# template_50x45.net
KiCad netlist of a schematic drawn in EAGLE
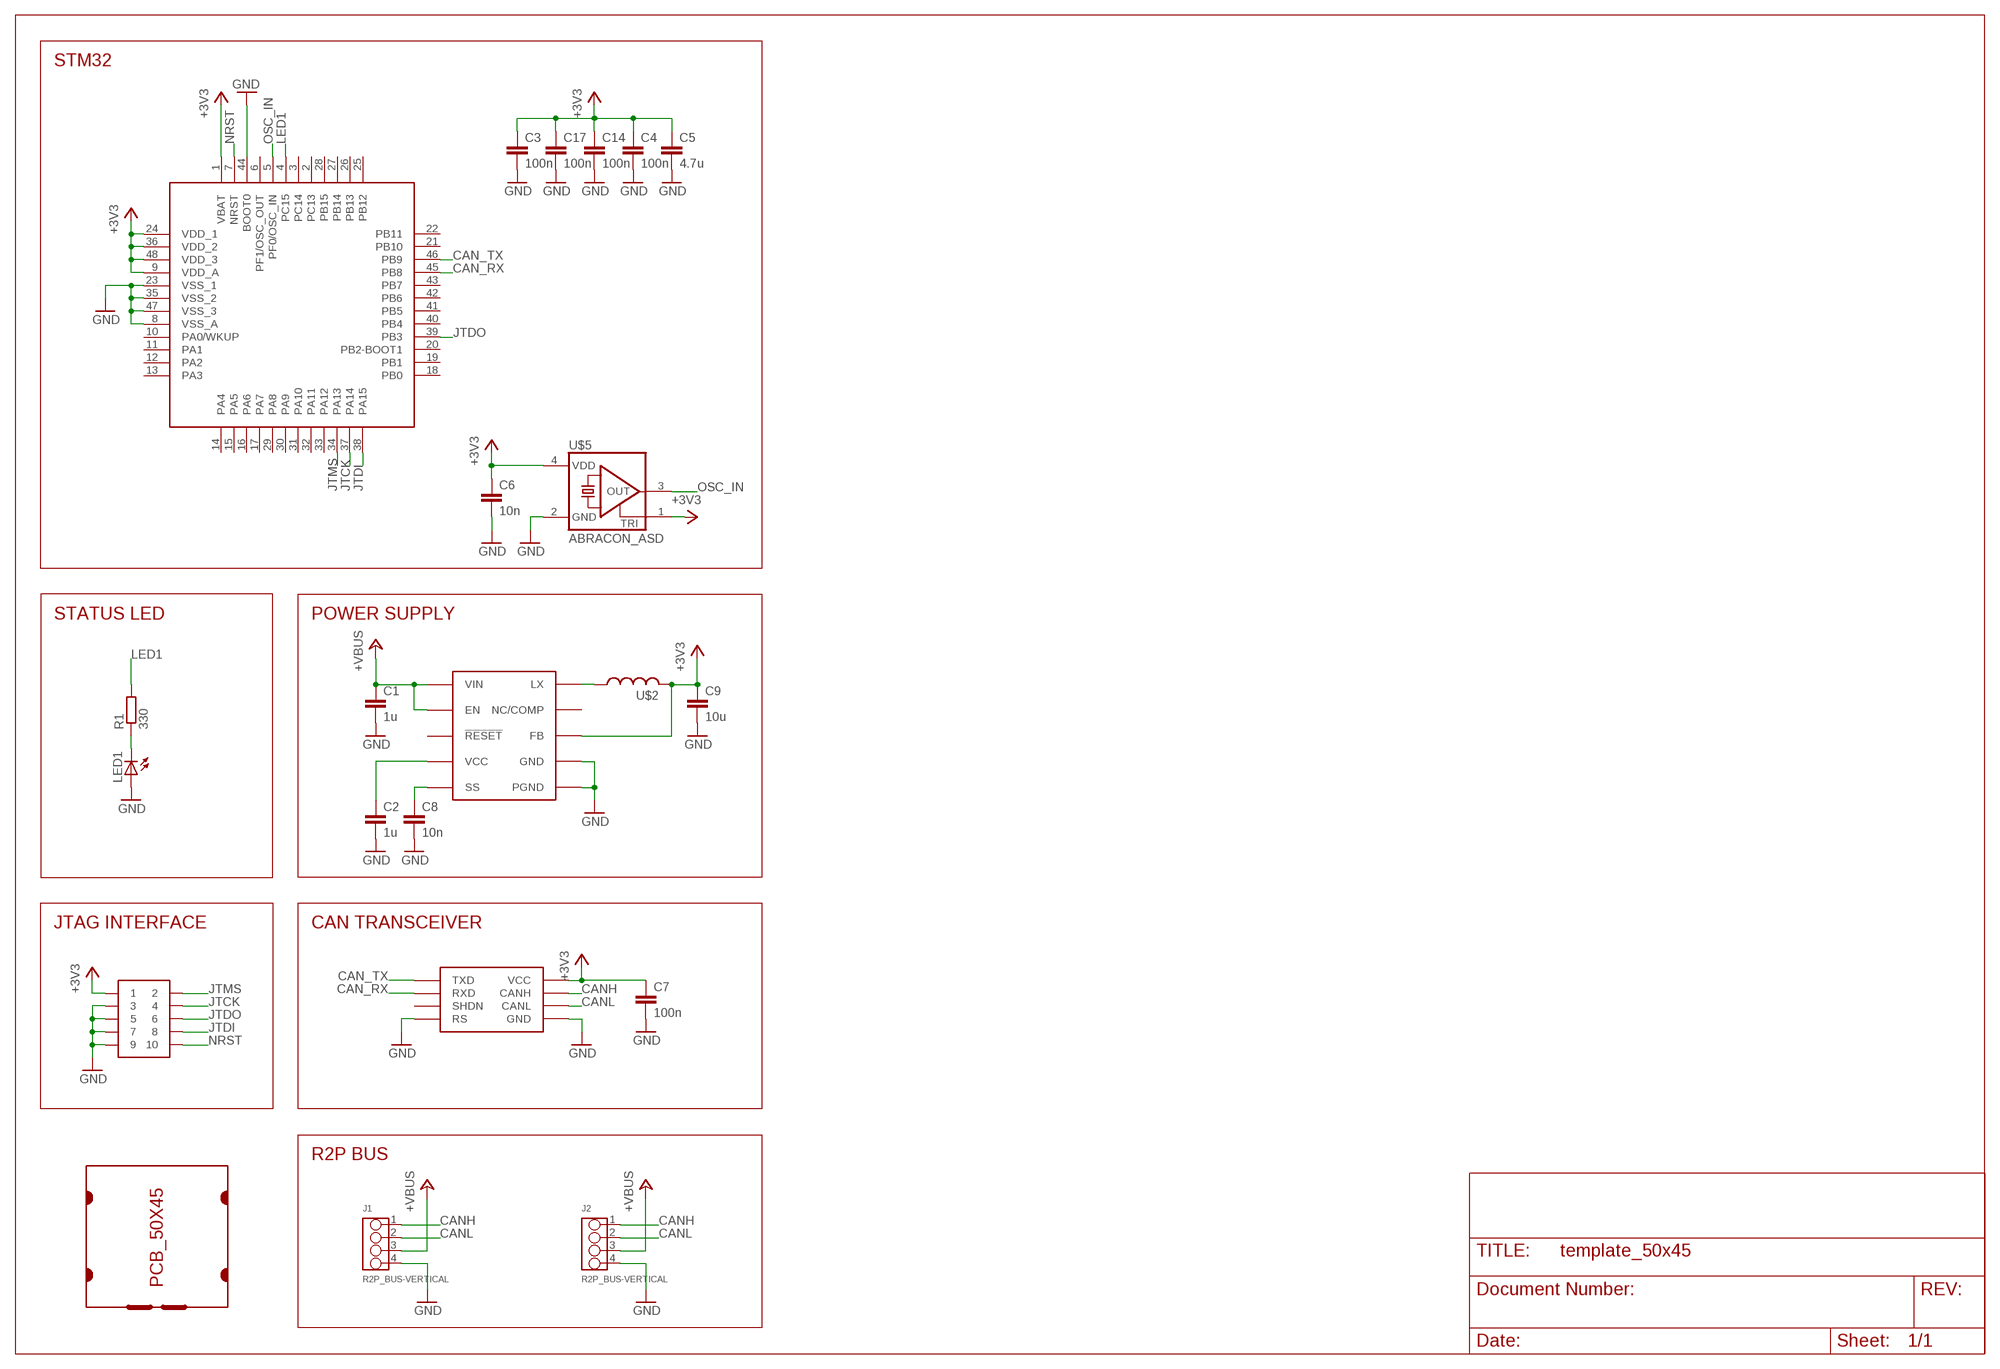
[diagram p0: schematic, sheet 1]

(export (version "E")
  (design (tool "Eeschema 10.0.6"))
  (components
    (comp (ref "C1")
      (value "1u")
      (footprint "eagle-import:C1206")
      (libsource (lib "eagle-import") (part "C1206"))
    )
    (comp (ref "C2")
      (value "1u")
      (footprint "eagle-import:C0603")
      (libsource (lib "eagle-import") (part "C0603"))
    )
    (comp (ref "C3")
      (value "100n")
      (footprint "eagle-import:C0603")
      (libsource (lib "eagle-import") (part "C0603"))
    )
    (comp (ref "C4")
      (value "100n")
      (footprint "eagle-import:C0603")
      (libsource (lib "eagle-import") (part "C0603"))
    )
    (comp (ref "C5")
      (value "4.7u")
      (footprint "eagle-import:C0805")
      (libsource (lib "eagle-import") (part "C0805"))
    )
    (comp (ref "C6")
      (value "10n")
      (footprint "eagle-import:C0603")
      (libsource (lib "eagle-import") (part "C0603"))
    )
    (comp (ref "C7")
      (value "100n")
      (footprint "eagle-import:C0603")
      (libsource (lib "eagle-import") (part "C0603"))
    )
    (comp (ref "C8")
      (value "10n")
      (footprint "eagle-import:C0603")
      (libsource (lib "eagle-import") (part "C0603"))
    )
    (comp (ref "C9")
      (value "10u")
      (footprint "eagle-import:C0805")
      (libsource (lib "eagle-import") (part "C0805"))
    )
    (comp (ref "C14")
      (value "100n")
      (footprint "eagle-import:C0603")
      (libsource (lib "eagle-import") (part "C0603"))
    )
    (comp (ref "C17")
      (value "100n")
      (footprint "eagle-import:C0603")
      (libsource (lib "eagle-import") (part "C0603"))
    )
    (comp (ref "J1")
      (value "R2P_BUS-VERTICAL")
      (footprint "eagle-import:OPL-EAGLE-LIBRARY_4P-2.0")
      (libsource (lib "eagle-import") (part "R2P_BUS-VERTICAL"))
    )
    (comp (ref "J2")
      (value "R2P_BUS-VERTICAL")
      (footprint "eagle-import:OPL-EAGLE-LIBRARY_4P-2.0")
      (libsource (lib "eagle-import") (part "R2P_BUS-VERTICAL"))
    )
    (comp (ref "LED1")
      (value "LED0805")
      (footprint "eagle-import:CHIPLED_0805")
      (libsource (lib "eagle-import") (part "LED0805"))
    )
    (comp (ref "R1")
      (value "330")
      (footprint "eagle-import:R0603")
      (libsource (lib "eagle-import") (part "R0603"))
    )
    (comp (ref "SOT1")
      (value "MAX3051EKA")
      (footprint "eagle-import:SOT23-8L")
      (libsource (lib "eagle-import") (part "MAX3051EKA"))
    )
    (comp (ref "U$1")
      (value "PCB_50X45")
      (footprint "eagle-import:50X45")
      (libsource (lib "eagle-import") (part "PCB_50X45"))
    )
    (comp (ref "U$2")
      (value "LPS4018")
      (footprint "eagle-import:COILCRAFT_LPS4018")
      (libsource (lib "eagle-import") (part "LPS4018"))
    )
    (comp (ref "U$3")
      (value "MAX17501")
      (footprint "eagle-import:TDFN-10")
      (libsource (lib "eagle-import") (part "MAX17501"))
    )
    (comp (ref "U$4")
      (value "JTAG-TH")
      (footprint "eagle-import:SAMTEC_FTSH-105-TH")
      (libsource (lib "eagle-import") (part "JTAG-TH"))
    )
    (comp (ref "U$5")
      (value "ABRACON_ASD")
      (footprint "eagle-import:ABRACON_2.5X2")
      (libsource (lib "eagle-import") (part "ABRACON_ASD"))
    )
    (comp (ref "U$6")
      (value "STM32F303CTX")
      (footprint "eagle-import:LQFP48")
      (libsource (lib "eagle-import") (part "STM32F303CTX"))
    )
  )
  (nets
    (net (code "1") (name "+3V3") (class "Default")
      (node (ref "C14") (pin "1") (pinfunction "1_1") (pintype "passive"))
      (node (ref "C17") (pin "1") (pinfunction "1_1") (pintype "passive"))
      (node (ref "C3") (pin "1") (pinfunction "1_1") (pintype "passive"))
      (node (ref "C4") (pin "1") (pinfunction "1_1") (pintype "passive"))
      (node (ref "C5") (pin "1") (pinfunction "1_1") (pintype "passive"))
      (node (ref "C6") (pin "1") (pinfunction "1_1") (pintype "passive"))
      (node (ref "C7") (pin "1") (pinfunction "1_1") (pintype "passive"))
      (node (ref "C9") (pin "1") (pinfunction "1_1") (pintype "passive"))
      (node (ref "SOT1") (pin "3") (pinfunction "VCC_3") (pintype "bidirectional"))
      (node (ref "U$2") (pin "P$2") (pinfunction "2_P$2") (pintype "passive"))
      (node (ref "U$3") (pin "P$5") (pinfunction "FB_P$5") (pintype "bidirectional"))
      (node (ref "U$4") (pin "1") (pinfunction "1_1") (pintype "bidirectional"))
      (node (ref "U$5") (pin "1") (pinfunction "TRI_1") (pintype "input"))
      (node (ref "U$5") (pin "4") (pinfunction "VDD_4") (pintype "power_in"))
      (node (ref "U$6") (pin "1") (pinfunction "VBAT_1") (pintype "bidirectional"))
      (node (ref "U$6") (pin "24") (pinfunction "VDD_1_24") (pintype "bidirectional"))
      (node (ref "U$6") (pin "36") (pinfunction "VDD_2_36") (pintype "bidirectional"))
      (node (ref "U$6") (pin "48") (pinfunction "VDD_3_48") (pintype "bidirectional"))
      (node (ref "U$6") (pin "9") (pinfunction "VDD_A_9") (pintype "bidirectional"))
    )
    (net (code "2") (name "+VBUS") (class "Default")
      (node (ref "C1") (pin "1") (pinfunction "1_1") (pintype "passive"))
      (node (ref "J1") (pin "3") (pinfunction "3_3") (pintype "bidirectional"))
      (node (ref "J2") (pin "3") (pinfunction "3_3") (pintype "bidirectional"))
      (node (ref "U$3") (pin "P$2") (pinfunction "VIN_P$2") (pintype "bidirectional"))
      (node (ref "U$3") (pin "P$3") (pinfunction "EN_P$3") (pintype "bidirectional"))
    )
    (net (code "3") (name "/CANH") (class "Default")
      (node (ref "J1") (pin "1") (pinfunction "1_1") (pintype "bidirectional"))
      (node (ref "J2") (pin "1") (pinfunction "1_1") (pintype "bidirectional"))
      (node (ref "SOT1") (pin "7") (pinfunction "CANH_7") (pintype "bidirectional"))
    )
    (net (code "4") (name "/CANL") (class "Default")
      (node (ref "J1") (pin "2") (pinfunction "2_2") (pintype "bidirectional"))
      (node (ref "J2") (pin "2") (pinfunction "2_2") (pintype "bidirectional"))
      (node (ref "SOT1") (pin "6") (pinfunction "CANL_6") (pintype "bidirectional"))
    )
    (net (code "5") (name "/CAN_RX") (class "Default")
      (node (ref "SOT1") (pin "4") (pinfunction "RXD_4") (pintype "bidirectional"))
      (node (ref "U$6") (pin "45") (pinfunction "PB8_45") (pintype "bidirectional"))
    )
    (net (code "6") (name "/CAN_TX") (class "Default")
      (node (ref "SOT1") (pin "1") (pinfunction "TXD_1") (pintype "bidirectional"))
      (node (ref "U$6") (pin "46") (pinfunction "PB9_46") (pintype "bidirectional"))
    )
    (net (code "7") (name "/JTCK") (class "Default")
      (node (ref "U$4") (pin "4") (pinfunction "4_4") (pintype "bidirectional"))
      (node (ref "U$6") (pin "37") (pinfunction "PA14_37") (pintype "bidirectional"))
    )
    (net (code "8") (name "/JTDI") (class "Default")
      (node (ref "U$4") (pin "8") (pinfunction "8_8") (pintype "bidirectional"))
      (node (ref "U$6") (pin "38") (pinfunction "PA15_38") (pintype "bidirectional"))
    )
    (net (code "9") (name "/JTDO") (class "Default")
      (node (ref "U$4") (pin "6") (pinfunction "6_6") (pintype "bidirectional"))
      (node (ref "U$6") (pin "39") (pinfunction "PB3_39") (pintype "bidirectional"))
    )
    (net (code "10") (name "/JTMS") (class "Default")
      (node (ref "U$4") (pin "2") (pinfunction "2_2") (pintype "bidirectional"))
      (node (ref "U$6") (pin "34") (pinfunction "PA13_34") (pintype "bidirectional"))
    )
    (net (code "11") (name "/LED1") (class "Default")
      (node (ref "R1") (pin "2") (pinfunction "2_2") (pintype "passive"))
      (node (ref "U$6") (pin "4") (pinfunction "PC15_4") (pintype "bidirectional"))
    )
    (net (code "12") (name "/NRST") (class "Default")
      (node (ref "U$4") (pin "10") (pinfunction "10_10") (pintype "bidirectional"))
      (node (ref "U$6") (pin "7") (pinfunction "NRST_7") (pintype "bidirectional"))
    )
    (net (code "13") (name "/OSC_IN") (class "Default")
      (node (ref "U$5") (pin "3") (pinfunction "OUT_3") (pintype "output"))
      (node (ref "U$6") (pin "5") (pinfunction "PF0/OSC_IN_5") (pintype "bidirectional"))
    )
    (net (code "14") (name "GND") (class "Default")
      (node (ref "C1") (pin "2") (pinfunction "2_2") (pintype "passive"))
      (node (ref "C14") (pin "2") (pinfunction "2_2") (pintype "passive"))
      (node (ref "C17") (pin "2") (pinfunction "2_2") (pintype "passive"))
      (node (ref "C2") (pin "2") (pinfunction "2_2") (pintype "passive"))
      (node (ref "C3") (pin "2") (pinfunction "2_2") (pintype "passive"))
      (node (ref "C4") (pin "2") (pinfunction "2_2") (pintype "passive"))
      (node (ref "C5") (pin "2") (pinfunction "2_2") (pintype "passive"))
      (node (ref "C6") (pin "2") (pinfunction "2_2") (pintype "passive"))
      (node (ref "C7") (pin "2") (pinfunction "2_2") (pintype "passive"))
      (node (ref "C8") (pin "2") (pinfunction "2_2") (pintype "passive"))
      (node (ref "C9") (pin "2") (pinfunction "2_2") (pintype "passive"))
      (node (ref "J1") (pin "4") (pinfunction "4_4") (pintype "bidirectional"))
      (node (ref "J2") (pin "4") (pinfunction "4_4") (pintype "bidirectional"))
      (node (ref "LED1") (pin "A") (pinfunction "A_A") (pintype "passive"))
      (node (ref "SOT1") (pin "2") (pinfunction "GND_2") (pintype "bidirectional"))
      (node (ref "SOT1") (pin "8") (pinfunction "RS_8") (pintype "bidirectional"))
      (node (ref "U$3") (pin "P$1") (pinfunction "PGND_P$1") (pintype "bidirectional"))
      (node (ref "U$3") (pin "P$11") (pinfunction "PGND_P$11") (pintype "bidirectional"))
      (node (ref "U$3") (pin "P$9") (pinfunction "GND_P$9") (pintype "bidirectional"))
      (node (ref "U$4") (pin "3") (pinfunction "3_3") (pintype "bidirectional"))
      (node (ref "U$4") (pin "5") (pinfunction "5_5") (pintype "bidirectional"))
      (node (ref "U$4") (pin "7") (pinfunction "7_7") (pintype "bidirectional"))
      (node (ref "U$4") (pin "9") (pinfunction "9_9") (pintype "bidirectional"))
      (node (ref "U$5") (pin "2") (pinfunction "GND_2") (pintype "power_in"))
      (node (ref "U$6") (pin "23") (pinfunction "VSS_1_23") (pintype "bidirectional"))
      (node (ref "U$6") (pin "35") (pinfunction "VSS_2_35") (pintype "bidirectional"))
      (node (ref "U$6") (pin "44") (pinfunction "BOOT0_44") (pintype "bidirectional"))
      (node (ref "U$6") (pin "47") (pinfunction "VSS_3_47") (pintype "bidirectional"))
      (node (ref "U$6") (pin "8") (pinfunction "VSS_A_8") (pintype "bidirectional"))
    )
    (net (code "15") (name "Net-(LED1-PadC)") (class "Default")
      (node (ref "LED1") (pin "C") (pinfunction "C_C") (pintype "passive"))
      (node (ref "R1") (pin "1") (pinfunction "1_1") (pintype "passive"))
    )
    (net (code "16") (name "Net-(U$2-1)") (class "Default")
      (node (ref "U$2") (pin "P$1") (pinfunction "1_P$1") (pintype "passive"))
      (node (ref "U$3") (pin "P$10") (pinfunction "LX_P$10") (pintype "bidirectional"))
    )
    (net (code "17") (name "Net-(U$3-SS)") (class "Default")
      (node (ref "C8") (pin "1") (pinfunction "1_1") (pintype "passive"))
      (node (ref "U$3") (pin "P$6") (pinfunction "SS_P$6") (pintype "bidirectional"))
    )
    (net (code "18") (name "Net-(U$3-VCC)") (class "Default")
      (node (ref "C2") (pin "1") (pinfunction "1_1") (pintype "passive"))
      (node (ref "U$3") (pin "P$4") (pinfunction "VCC_P$4") (pintype "bidirectional"))
    )
    (net (code "19") (name "unconnected-(SOT1-SHDN-Pad5)") (class "Default")
      (node (ref "SOT1") (pin "5") (pinfunction "SHDN_5") (pintype "bidirectional"))
    )
    (net (code "20") (name "unconnected-(U$3-NC{slash}COMP-PadP$7)") (class "Default")
      (node (ref "U$3") (pin "P$7") (pinfunction "NC/COMP_P$7") (pintype "bidirectional"))
    )
    (net (code "21") (name "unconnected-(U$3-~{RESET}-PadP$8)") (class "Default")
      (node (ref "U$3") (pin "P$8") (pinfunction "~{RESET}_P$8") (pintype "bidirectional"))
    )
    (net (code "22") (name "unconnected-(U$6-PA0{slash}WKUP-Pad10)") (class "Default")
      (node (ref "U$6") (pin "10") (pinfunction "PA0/WKUP_10") (pintype "bidirectional"))
    )
    (net (code "23") (name "unconnected-(U$6-PA1-Pad11)") (class "Default")
      (node (ref "U$6") (pin "11") (pinfunction "PA1_11") (pintype "bidirectional"))
    )
    (net (code "24") (name "unconnected-(U$6-PA2-Pad12)") (class "Default")
      (node (ref "U$6") (pin "12") (pinfunction "PA2_12") (pintype "bidirectional"))
    )
    (net (code "25") (name "unconnected-(U$6-PA3-Pad13)") (class "Default")
      (node (ref "U$6") (pin "13") (pinfunction "PA3_13") (pintype "bidirectional"))
    )
    (net (code "26") (name "unconnected-(U$6-PA4-Pad14)") (class "Default")
      (node (ref "U$6") (pin "14") (pinfunction "PA4_14") (pintype "bidirectional"))
    )
    (net (code "27") (name "unconnected-(U$6-PA5-Pad15)") (class "Default")
      (node (ref "U$6") (pin "15") (pinfunction "PA5_15") (pintype "bidirectional"))
    )
    (net (code "28") (name "unconnected-(U$6-PA6-Pad16)") (class "Default")
      (node (ref "U$6") (pin "16") (pinfunction "PA6_16") (pintype "bidirectional"))
    )
    (net (code "29") (name "unconnected-(U$6-PA7-Pad17)") (class "Default")
      (node (ref "U$6") (pin "17") (pinfunction "PA7_17") (pintype "bidirectional"))
    )
    (net (code "30") (name "unconnected-(U$6-PA8-Pad29)") (class "Default")
      (node (ref "U$6") (pin "29") (pinfunction "PA8_29") (pintype "bidirectional"))
    )
    (net (code "31") (name "unconnected-(U$6-PA9-Pad30)") (class "Default")
      (node (ref "U$6") (pin "30") (pinfunction "PA9_30") (pintype "bidirectional"))
    )
    (net (code "32") (name "unconnected-(U$6-PA10-Pad31)") (class "Default")
      (node (ref "U$6") (pin "31") (pinfunction "PA10_31") (pintype "bidirectional"))
    )
    (net (code "33") (name "unconnected-(U$6-PA11-Pad32)") (class "Default")
      (node (ref "U$6") (pin "32") (pinfunction "PA11_32") (pintype "bidirectional"))
    )
    (net (code "34") (name "unconnected-(U$6-PA12-Pad33)") (class "Default")
      (node (ref "U$6") (pin "33") (pinfunction "PA12_33") (pintype "bidirectional"))
    )
    (net (code "35") (name "unconnected-(U$6-PB0-Pad18)") (class "Default")
      (node (ref "U$6") (pin "18") (pinfunction "PB0_18") (pintype "bidirectional"))
    )
    (net (code "36") (name "unconnected-(U$6-PB1-Pad19)") (class "Default")
      (node (ref "U$6") (pin "19") (pinfunction "PB1_19") (pintype "bidirectional"))
    )
    (net (code "37") (name "unconnected-(U$6-PB2-BOOT1-Pad20)") (class "Default")
      (node (ref "U$6") (pin "20") (pinfunction "PB2-BOOT1_20") (pintype "bidirectional"))
    )
    (net (code "38") (name "unconnected-(U$6-PB4-Pad40)") (class "Default")
      (node (ref "U$6") (pin "40") (pinfunction "PB4_40") (pintype "bidirectional"))
    )
    (net (code "39") (name "unconnected-(U$6-PB5-Pad41)") (class "Default")
      (node (ref "U$6") (pin "41") (pinfunction "PB5_41") (pintype "bidirectional"))
    )
    (net (code "40") (name "unconnected-(U$6-PB6-Pad42)") (class "Default")
      (node (ref "U$6") (pin "42") (pinfunction "PB6_42") (pintype "bidirectional"))
    )
    (net (code "41") (name "unconnected-(U$6-PB7-Pad43)") (class "Default")
      (node (ref "U$6") (pin "43") (pinfunction "PB7_43") (pintype "bidirectional"))
    )
    (net (code "42") (name "unconnected-(U$6-PB10-Pad21)") (class "Default")
      (node (ref "U$6") (pin "21") (pinfunction "PB10_21") (pintype "bidirectional"))
    )
    (net (code "43") (name "unconnected-(U$6-PB11-Pad22)") (class "Default")
      (node (ref "U$6") (pin "22") (pinfunction "PB11_22") (pintype "bidirectional"))
    )
    (net (code "44") (name "unconnected-(U$6-PB12-Pad25)") (class "Default")
      (node (ref "U$6") (pin "25") (pinfunction "PB12_25") (pintype "bidirectional"))
    )
    (net (code "45") (name "unconnected-(U$6-PB13-Pad26)") (class "Default")
      (node (ref "U$6") (pin "26") (pinfunction "PB13_26") (pintype "bidirectional"))
    )
    (net (code "46") (name "unconnected-(U$6-PB14-Pad27)") (class "Default")
      (node (ref "U$6") (pin "27") (pinfunction "PB14_27") (pintype "bidirectional"))
    )
    (net (code "47") (name "unconnected-(U$6-PB15-Pad28)") (class "Default")
      (node (ref "U$6") (pin "28") (pinfunction "PB15_28") (pintype "bidirectional"))
    )
    (net (code "48") (name "unconnected-(U$6-PC13-Pad2)") (class "Default")
      (node (ref "U$6") (pin "2") (pinfunction "PC13_2") (pintype "bidirectional"))
    )
    (net (code "49") (name "unconnected-(U$6-PC14-Pad3)") (class "Default")
      (node (ref "U$6") (pin "3") (pinfunction "PC14_3") (pintype "bidirectional"))
    )
    (net (code "50") (name "unconnected-(U$6-PF1{slash}OSC_OUT-Pad6)") (class "Default")
      (node (ref "U$6") (pin "6") (pinfunction "PF1/OSC_OUT_6") (pintype "bidirectional"))
    )
  )
)
